# HaD_Arduino.net
KiCad netlist of a schematic drawn in EAGLE
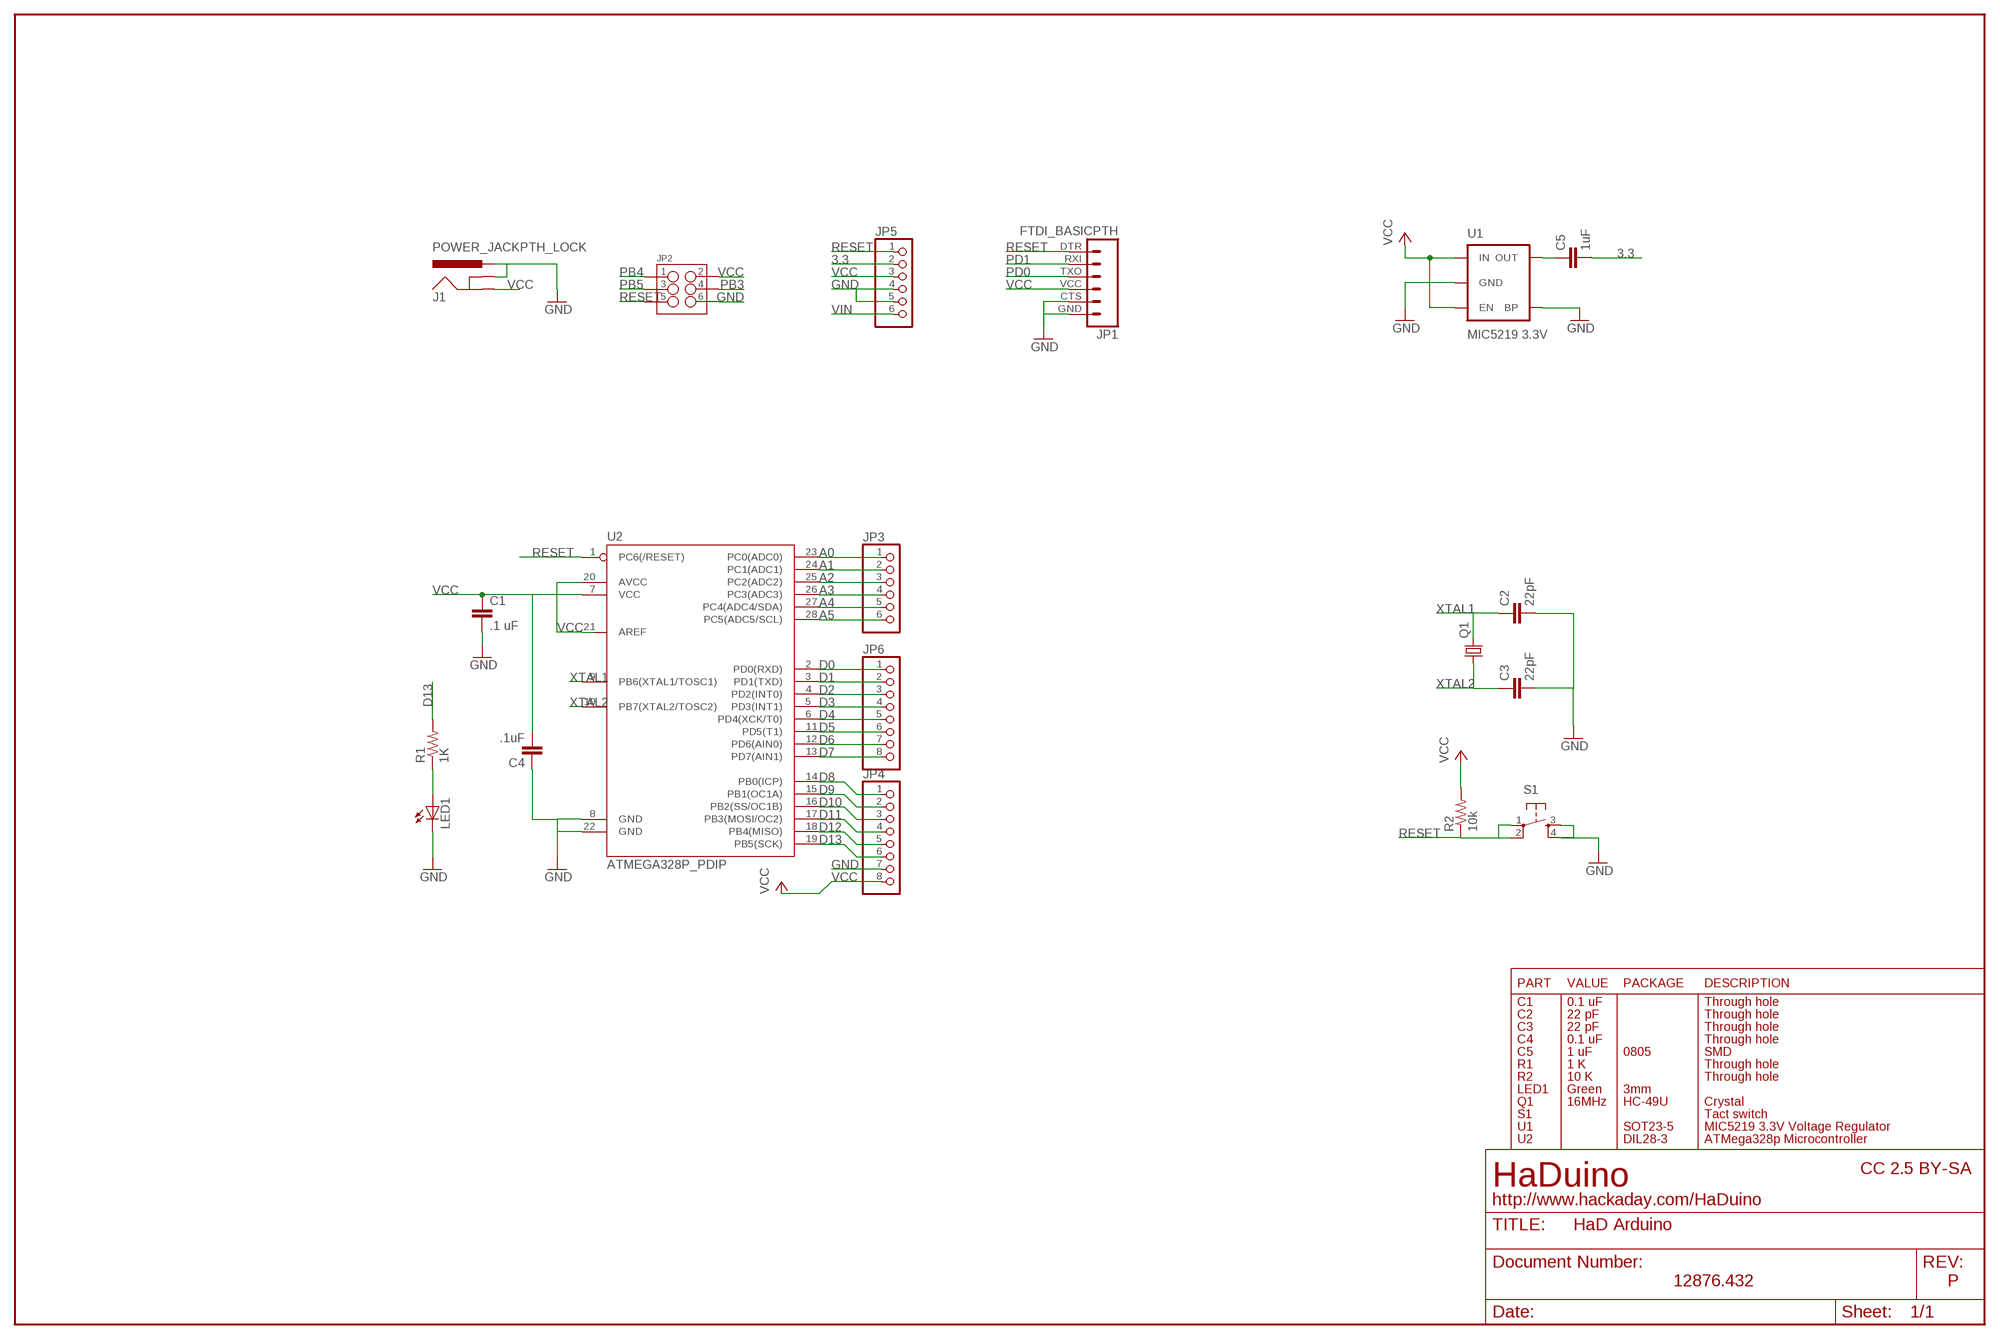
[diagram p0: schematic, sheet 1]

(export (version "E")
  (design (tool "Eeschema 10.0.6"))
  (components
    (comp (ref "C1")
      (value ".1 uF")
      (footprint "eagle-import:CAP-PTH-SMALL-KIT")
      (libsource (lib "eagle-import") (part "CAPKIT"))
    )
    (comp (ref "C2")
      (value "22pF")
      (footprint "eagle-import:CAP-PTH-SMALL-KIT")
      (libsource (lib "eagle-import") (part "CAPKIT"))
    )
    (comp (ref "C3")
      (value "22pF")
      (footprint "eagle-import:CAP-PTH-SMALL-KIT")
      (libsource (lib "eagle-import") (part "CAPKIT"))
    )
    (comp (ref "C4")
      (value ".1uF")
      (footprint "eagle-import:CAP-PTH-SMALL-KIT")
      (libsource (lib "eagle-import") (part "CAPKIT"))
    )
    (comp (ref "C5")
      (value "1uF")
      (footprint "eagle-import:0805")
      (libsource (lib "eagle-import") (part "1UF-25V-10%(0805)"))
    )
    (comp (ref "J1")
      (value "POWER_JACKPTH_LOCK")
      (footprint "eagle-import:POWER_JACK_PTH_LOCK")
      (libsource (lib "eagle-import") (part "POWER_JACKPTH_LOCK"))
    )
    (comp (ref "JP1")
      (value "FTDI_BASICPTH")
      (footprint "eagle-import:FTDI_BASIC")
      (libsource (lib "eagle-import") (part "FTDI_BASICPTH"))
    )
    (comp (ref "JP2")
      (value "M03X2POGO_PINS")
      (footprint "eagle-import:2X3_POGO")
      (libsource (lib "eagle-import") (part "M03X2POGO_PINS"))
    )
    (comp (ref "JP3")
      (value "PINHD-1X6B")
      (footprint "eagle-import:1X06-BIG")
      (libsource (lib "eagle-import") (part "PINHD-1X6B"))
    )
    (comp (ref "JP4")
      (value "PINHD-1X8BIG")
      (footprint "eagle-import:1X08-BIG")
      (libsource (lib "eagle-import") (part "PINHD-1X8BIG"))
    )
    (comp (ref "JP5")
      (value "PINHD-1X6B")
      (footprint "eagle-import:1X06-BIG")
      (libsource (lib "eagle-import") (part "PINHD-1X6B"))
    )
    (comp (ref "JP6")
      (value "PINHD-1X8BIG")
      (footprint "eagle-import:1X08-BIG")
      (libsource (lib "eagle-import") (part "PINHD-1X8BIG"))
    )
    (comp (ref "LED1")
      (value "LED3MM")
      (footprint "eagle-import:LED3MM")
      (libsource (lib "eagle-import") (part "LED3MM"))
    )
    (comp (ref "Q1")
      (value "CRYTALHC49U-V")
      (footprint "eagle-import:HC49U-V")
      (libsource (lib "eagle-import") (part "CRYTALHC49U-V"))
    )
    (comp (ref "R1")
      (value "1K")
      (footprint "eagle-import:AXIAL-0.3-KIT")
      (libsource (lib "eagle-import") (part "RESISTORKIT"))
    )
    (comp (ref "R2")
      (value "10k")
      (footprint "eagle-import:AXIAL-0.3-KIT")
      (libsource (lib "eagle-import") (part "SparkFun-Resistors_RESISTORKIT"))
    )
    (comp (ref "S1")
      (value "TAC_SWITCHPTH")
      (footprint "eagle-import:TACTILE-PTH")
      (libsource (lib "eagle-import") (part "TAC_SWITCHPTH"))
    )
    (comp (ref "U1")
      (value "MIC5219 3.3V")
      (footprint "eagle-import:SOT23-5")
      (libsource (lib "eagle-import") (part "V_REG_MIC52193.3V"))
    )
    (comp (ref "U2")
      (value "ATMEGA328P_PDIP")
      (footprint "eagle-import:DIL28-3")
      (libsource (lib "eagle-import") (part "ATMEGA328P_PDIP"))
    )
  )
  (nets
    (net (code "1") (name "/3.3") (class "Default")
      (node (ref "C5") (pin "2") (pinfunction "2_2") (pintype "passive"))
      (node (ref "JP5") (pin "2") (pinfunction "2_2") (pintype "passive"))
    )
    (net (code "2") (name "/A0") (class "Default")
      (node (ref "JP3") (pin "1") (pinfunction "1_1") (pintype "passive"))
      (node (ref "U2") (pin "23") (pinfunction "PC0(ADC0)_23") (pintype "bidirectional"))
    )
    (net (code "3") (name "/A1") (class "Default")
      (node (ref "JP3") (pin "2") (pinfunction "2_2") (pintype "passive"))
      (node (ref "U2") (pin "24") (pinfunction "PC1(ADC1)_24") (pintype "bidirectional"))
    )
    (net (code "4") (name "/A2") (class "Default")
      (node (ref "JP3") (pin "3") (pinfunction "3_3") (pintype "passive"))
      (node (ref "U2") (pin "25") (pinfunction "PC2(ADC2)_25") (pintype "bidirectional"))
    )
    (net (code "5") (name "/A3") (class "Default")
      (node (ref "JP3") (pin "4") (pinfunction "4_4") (pintype "passive"))
      (node (ref "U2") (pin "26") (pinfunction "PC3(ADC3)_26") (pintype "bidirectional"))
    )
    (net (code "6") (name "/A4") (class "Default")
      (node (ref "JP3") (pin "5") (pinfunction "5_5") (pintype "passive"))
      (node (ref "U2") (pin "27") (pinfunction "PC4(ADC4/SDA)_27") (pintype "bidirectional"))
    )
    (net (code "7") (name "/A5") (class "Default")
      (node (ref "JP3") (pin "6") (pinfunction "6_6") (pintype "passive"))
      (node (ref "U2") (pin "28") (pinfunction "PC5(ADC5/SCL)_28") (pintype "bidirectional"))
    )
    (net (code "8") (name "/D0") (class "Default")
      (node (ref "JP6") (pin "1") (pinfunction "1_1") (pintype "passive"))
      (node (ref "U2") (pin "2") (pinfunction "PD0(RXD)_2") (pintype "bidirectional"))
    )
    (net (code "9") (name "/D1") (class "Default")
      (node (ref "JP6") (pin "2") (pinfunction "2_2") (pintype "passive"))
      (node (ref "U2") (pin "3") (pinfunction "PD1(TXD)_3") (pintype "bidirectional"))
    )
    (net (code "10") (name "/D2") (class "Default")
      (node (ref "JP6") (pin "3") (pinfunction "3_3") (pintype "passive"))
      (node (ref "U2") (pin "4") (pinfunction "PD2(INT0)_4") (pintype "bidirectional"))
    )
    (net (code "11") (name "/D3") (class "Default")
      (node (ref "JP6") (pin "4") (pinfunction "4_4") (pintype "passive"))
      (node (ref "U2") (pin "5") (pinfunction "PD3(INT1)_5") (pintype "bidirectional"))
    )
    (net (code "12") (name "/D4") (class "Default")
      (node (ref "JP6") (pin "5") (pinfunction "5_5") (pintype "passive"))
      (node (ref "U2") (pin "6") (pinfunction "PD4(XCK/T0)_6") (pintype "bidirectional"))
    )
    (net (code "13") (name "/D5") (class "Default")
      (node (ref "JP6") (pin "6") (pinfunction "6_6") (pintype "passive"))
      (node (ref "U2") (pin "11") (pinfunction "PD5(T1)_11") (pintype "bidirectional"))
    )
    (net (code "14") (name "/D6") (class "Default")
      (node (ref "JP6") (pin "7") (pinfunction "7_7") (pintype "passive"))
      (node (ref "U2") (pin "12") (pinfunction "PD6(AIN0)_12") (pintype "bidirectional"))
    )
    (net (code "15") (name "/D7") (class "Default")
      (node (ref "JP6") (pin "8") (pinfunction "8_8") (pintype "passive"))
      (node (ref "U2") (pin "13") (pinfunction "PD7(AIN1)_13") (pintype "bidirectional"))
    )
    (net (code "16") (name "/D8") (class "Default")
      (node (ref "JP4") (pin "1") (pinfunction "1_1") (pintype "passive"))
      (node (ref "U2") (pin "14") (pinfunction "PB0(ICP)_14") (pintype "bidirectional"))
    )
    (net (code "17") (name "/D9") (class "Default")
      (node (ref "JP4") (pin "2") (pinfunction "2_2") (pintype "passive"))
      (node (ref "U2") (pin "15") (pinfunction "PB1(OC1A)_15") (pintype "bidirectional"))
    )
    (net (code "18") (name "/D10") (class "Default")
      (node (ref "JP4") (pin "3") (pinfunction "3_3") (pintype "passive"))
      (node (ref "U2") (pin "16") (pinfunction "PB2(SS/OC1B)_16") (pintype "bidirectional"))
    )
    (net (code "19") (name "/D11") (class "Default")
      (node (ref "JP4") (pin "4") (pinfunction "4_4") (pintype "passive"))
      (node (ref "U2") (pin "17") (pinfunction "PB3(MOSI/OC2)_17") (pintype "bidirectional"))
    )
    (net (code "20") (name "/D12") (class "Default")
      (node (ref "JP4") (pin "5") (pinfunction "5_5") (pintype "passive"))
      (node (ref "U2") (pin "18") (pinfunction "PB4(MISO)_18") (pintype "bidirectional"))
    )
    (net (code "21") (name "/D13") (class "Default")
      (node (ref "JP4") (pin "6") (pinfunction "6_6") (pintype "passive"))
      (node (ref "R1") (pin "P$2") (pinfunction "2_P$2") (pintype "passive"))
      (node (ref "U2") (pin "19") (pinfunction "PB5(SCK)_19") (pintype "bidirectional"))
    )
    (net (code "22") (name "/PB3") (class "Default")
      (node (ref "JP2") (pin "P$4") (pinfunction "4_P$4") (pintype "bidirectional"))
    )
    (net (code "23") (name "/PB4") (class "Default")
      (node (ref "JP2") (pin "P$1") (pinfunction "1_P$1") (pintype "bidirectional"))
    )
    (net (code "24") (name "/PB5") (class "Default")
      (node (ref "JP2") (pin "P$3") (pinfunction "3_P$3") (pintype "bidirectional"))
    )
    (net (code "25") (name "/PD0") (class "Default")
      (node (ref "JP1") (pin "TXO") (pinfunction "3_TXO") (pintype "passive"))
    )
    (net (code "26") (name "/PD1") (class "Default")
      (node (ref "JP1") (pin "RXI") (pinfunction "2_RXI") (pintype "passive"))
    )
    (net (code "27") (name "/RESET") (class "Default")
      (node (ref "JP1") (pin "DTR") (pinfunction "1_DTR") (pintype "passive"))
      (node (ref "JP2") (pin "P$5") (pinfunction "5_P$5") (pintype "bidirectional"))
      (node (ref "JP5") (pin "1") (pinfunction "1_1") (pintype "passive"))
      (node (ref "R2") (pin "P$1") (pinfunction "1_P$1") (pintype "passive"))
      (node (ref "S1") (pin "1") (pinfunction "1_1") (pintype "passive"))
      (node (ref "S1") (pin "2") (pinfunction "2_2") (pintype "passive"))
      (node (ref "U2") (pin "1") (pinfunction "PC6(/RESET)_1") (pintype "bidirectional"))
    )
    (net (code "28") (name "/VIN") (class "Default")
      (node (ref "JP5") (pin "6") (pinfunction "6_6") (pintype "passive"))
    )
    (net (code "29") (name "/XTAL1") (class "Default")
      (node (ref "C2") (pin "1") (pinfunction "1_1") (pintype "passive"))
      (node (ref "Q1") (pin "2") (pinfunction "2_2") (pintype "passive"))
      (node (ref "U2") (pin "9") (pinfunction "PB6(XTAL1/TOSC1)_9") (pintype "bidirectional"))
    )
    (net (code "30") (name "/XTAL2") (class "Default")
      (node (ref "C3") (pin "1") (pinfunction "1_1") (pintype "passive"))
      (node (ref "Q1") (pin "1") (pinfunction "1_1") (pintype "passive"))
      (node (ref "U2") (pin "10") (pinfunction "PB7(XTAL2/TOSC2)_10") (pintype "bidirectional"))
    )
    (net (code "31") (name "GND") (class "Default")
      (node (ref "C1") (pin "2") (pinfunction "2_2") (pintype "passive"))
      (node (ref "C2") (pin "2") (pinfunction "2_2") (pintype "passive"))
      (node (ref "C3") (pin "2") (pinfunction "2_2") (pintype "passive"))
      (node (ref "C4") (pin "1") (pinfunction "1_1") (pintype "passive"))
      (node (ref "J1") (pin "GNDBREAK") (pinfunction "GNDBREAK_GNDBREAK") (pintype "bidirectional"))
      (node (ref "J1") (pin "PWR") (pinfunction "PWR_PWR") (pintype "bidirectional"))
      (node (ref "JP1") (pin "CTS") (pinfunction "5_CTS") (pintype "passive"))
      (node (ref "JP1") (pin "GND") (pinfunction "6_GND") (pintype "passive"))
      (node (ref "JP2") (pin "P$6") (pinfunction "6_P$6") (pintype "bidirectional"))
      (node (ref "JP4") (pin "7") (pinfunction "7_7") (pintype "passive"))
      (node (ref "JP5") (pin "4") (pinfunction "4_4") (pintype "passive"))
      (node (ref "JP5") (pin "5") (pinfunction "5_5") (pintype "passive"))
      (node (ref "LED1") (pin "K") (pinfunction "C_K") (pintype "passive"))
      (node (ref "S1") (pin "3") (pinfunction "3_3") (pintype "passive"))
      (node (ref "S1") (pin "4") (pinfunction "4_4") (pintype "passive"))
      (node (ref "U1") (pin "2") (pinfunction "GND_2") (pintype "input"))
      (node (ref "U1") (pin "4") (pinfunction "BP_4") (pintype "input"))
      (node (ref "U2") (pin "22") (pinfunction "GND_22") (pintype "bidirectional"))
      (node (ref "U2") (pin "8") (pinfunction "GND_8") (pintype "bidirectional"))
    )
    (net (code "32") (name "Net-(R1-1)") (class "Default")
      (node (ref "LED1") (pin "A") (pinfunction "A_A") (pintype "passive"))
      (node (ref "R1") (pin "P$1") (pinfunction "1_P$1") (pintype "passive"))
    )
    (net (code "33") (name "Net-(U1-OUT)") (class "Default")
      (node (ref "C5") (pin "1") (pinfunction "1_1") (pintype "passive"))
      (node (ref "U1") (pin "5") (pinfunction "OUT_5") (pintype "passive"))
    )
    (net (code "34") (name "VCC") (class "Default")
      (node (ref "C1") (pin "1") (pinfunction "1_1") (pintype "passive"))
      (node (ref "C4") (pin "2") (pinfunction "2_2") (pintype "passive"))
      (node (ref "J1") (pin "GND") (pinfunction "GND_GND") (pintype "bidirectional"))
      (node (ref "JP1") (pin "VCC") (pinfunction "4_VCC") (pintype "passive"))
      (node (ref "JP2") (pin "P$2") (pinfunction "2_P$2") (pintype "bidirectional"))
      (node (ref "JP4") (pin "8") (pinfunction "8_8") (pintype "passive"))
      (node (ref "JP5") (pin "3") (pinfunction "3_3") (pintype "passive"))
      (node (ref "R2") (pin "P$2") (pinfunction "2_P$2") (pintype "passive"))
      (node (ref "U1") (pin "1") (pinfunction "IN_1") (pintype "input"))
      (node (ref "U1") (pin "3") (pinfunction "EN_3") (pintype "input"))
      (node (ref "U2") (pin "20") (pinfunction "AVCC_20") (pintype "bidirectional"))
      (node (ref "U2") (pin "21") (pinfunction "AREF_21") (pintype "bidirectional"))
      (node (ref "U2") (pin "7") (pinfunction "VCC_7") (pintype "bidirectional"))
    )
  )
)
